# LipSync_Mini_Main_Board.net
KiCad netlist of a schematic drawn in EAGLE
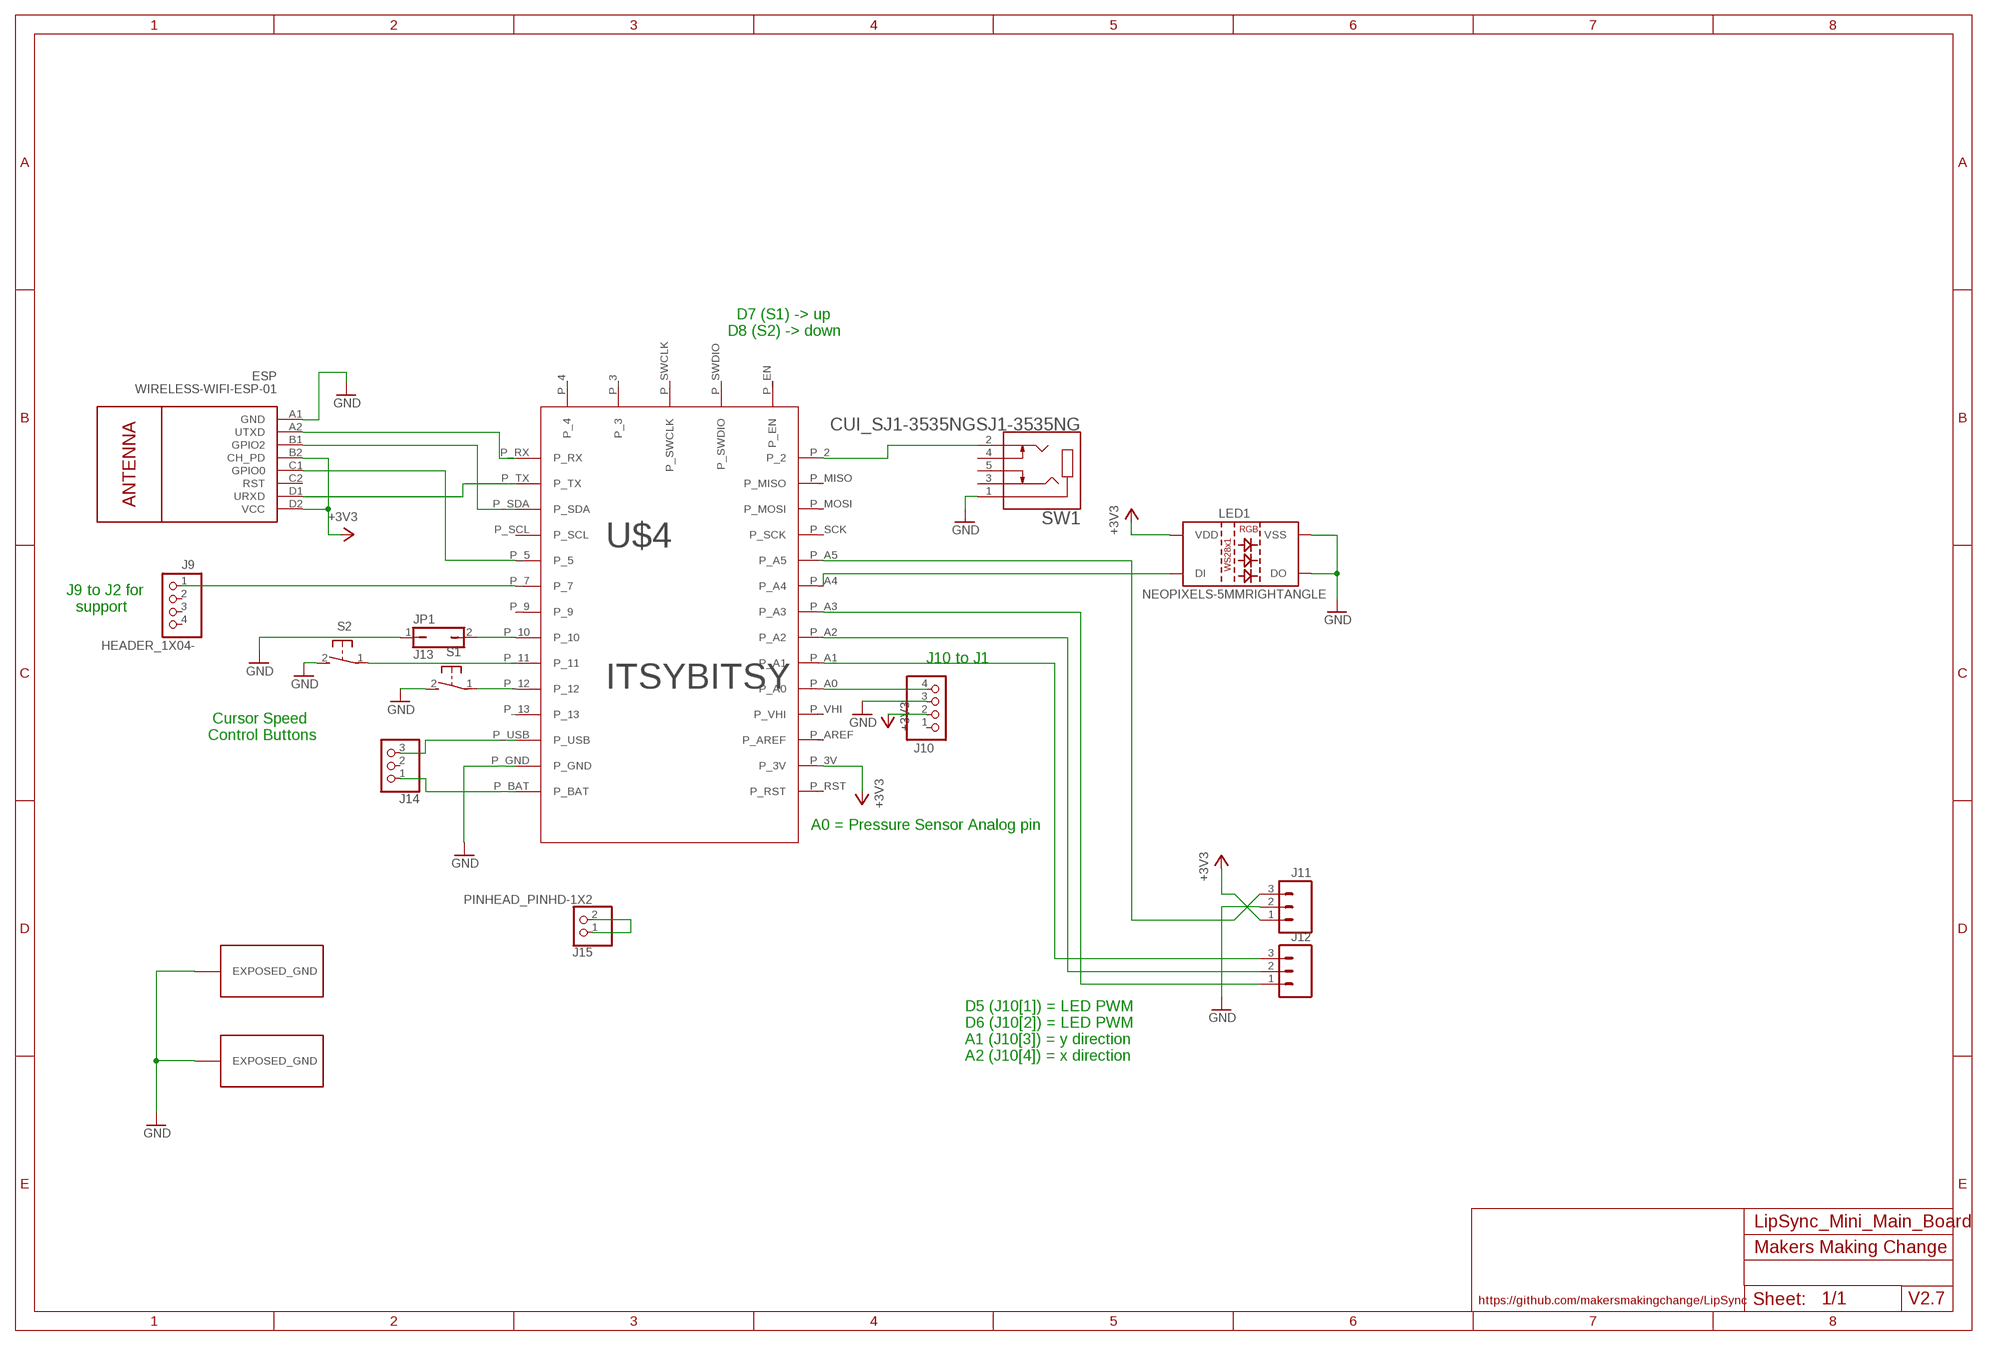
[diagram p0: schematic, sheet 1]

(export (version "E")
  (design (tool "Eeschema 10.0.6"))
  (components
    (comp (ref "ESP")
      (value "WIRELESS-WIFI-ESP-01")
      (footprint "eagle-import:WIRELESS-WIFI-ESP-01")
      (libsource (lib "eagle-import") (part "WIRELESS-WIFI-ESP-01"))
    )
    (comp (ref "J9")
      (value "HEADER_1X04-")
      (footprint "eagle-import:1X04")
      (libsource (lib "eagle-import") (part "HEADER_1X04-"))
    )
    (comp (ref "J10")
      (value "HEADER_1X04-")
      (footprint "eagle-import:1X04")
      (libsource (lib "eagle-import") (part "HEADER_1X04-"))
    )
    (comp (ref "J11")
      (value "HEADER_1X03-/90")
      (footprint "eagle-import:1X03_LOCK_90")
      (libsource (lib "eagle-import") (part "HEADER_1X03-/90"))
    )
    (comp (ref "J12")
      (value "HEADER_1X03-/90")
      (footprint "eagle-import:1X03_LOCK_90")
      (libsource (lib "eagle-import") (part "HEADER_1X03-/90"))
    )
    (comp (ref "J13")
      (value "JP1")
      (footprint "eagle-import:JP1")
      (libsource (lib "eagle-import") (part "JP1"))
    )
    (comp (ref "J14")
      (value "PINHEAD_PINHD-1X3")
      (footprint "eagle-import:PINHEAD_1X03")
      (libsource (lib "eagle-import") (part "PINHEAD_PINHD-1X3"))
    )
    (comp (ref "J15")
      (value "PINHEAD_PINHD-1X2")
      (footprint "eagle-import:PINHEAD_1X02")
      (libsource (lib "eagle-import") (part "PINHEAD_PINHD-1X2"))
    )
    (comp (ref "LED1")
      (value "NEOPIXELS-5MMRIGHTANGLE")
      (footprint "eagle-import:NEOPIXELS-RIGHTANGLE-5MM")
      (libsource (lib "eagle-import") (part "NEOPIXELS-5MMRIGHTANGLE"))
    )
    (comp (ref "S1")
      (value "B3F_31-XXSKINNY")
      (footprint "eagle-import:B3F-31XX-SKINNIER")
      (libsource (lib "eagle-import") (part "B3F_31-XXSKINNY"))
    )
    (comp (ref "S2")
      (value "B3F_31-XXSKINNY")
      (footprint "eagle-import:B3F-31XX-SKINNIER")
      (libsource (lib "eagle-import") (part "B3F_31-XXSKINNY"))
    )
    (comp (ref "SW1")
      (value "CUI_SJ1-3535NGSJ1-3535NG")
      (footprint "eagle-import:CUI_SJ1-3535NG")
      (libsource (lib "eagle-import") (part "CUI_SJ1-3535NGSJ1-3535NG"))
    )
    (comp (ref "U$2")
      (value "EXPOSED_GND")
      (footprint "eagle-import:EXPOSED_GND")
      (libsource (lib "eagle-import") (part "EXPOSED_GND"))
    )
    (comp (ref "U$3")
      (value "EXPOSED_GND")
      (footprint "eagle-import:EXPOSED_GND")
      (libsource (lib "eagle-import") (part "MMC Eagle_13126479_EXPOSED_GND"))
    )
    (comp (ref "U$4")
      (value "ITSYBITSY")
      (footprint "eagle-import:ITSYBITSY")
      (libsource (lib "eagle-import") (part "ITSYBITSY"))
    )
  )
  (nets
    (net (code "1") (name "+3V3") (class "Default")
      (node (ref "ESP") (pin "B2") (pinfunction "CH_PD_B2") (pintype "bidirectional"))
      (node (ref "ESP") (pin "D2") (pinfunction "VCC_D2") (pintype "power_in"))
      (node (ref "J10") (pin "2") (pinfunction "2_2") (pintype "passive"))
      (node (ref "J11") (pin "1") (pinfunction "1_1") (pintype "passive"))
      (node (ref "LED1") (pin "P2") (pinfunction "VDD_P2") (pintype "bidirectional"))
      (node (ref "U$4") (pin "P_3V") (pinfunction "P_3V_P_3V") (pintype "bidirectional"))
    )
    (net (code "2") (name "EXPOSED_GND") (class "Default")
      (node (ref "ESP") (pin "A1") (pinfunction "GND_A1") (pintype "power_in"))
      (node (ref "J10") (pin "3") (pinfunction "3_3") (pintype "passive"))
      (node (ref "J11") (pin "2") (pinfunction "2_2") (pintype "passive"))
      (node (ref "J13") (pin "1") (pinfunction "1_1") (pintype "passive"))
      (node (ref "LED1") (pin "P3") (pinfunction "VSS_P3") (pintype "bidirectional"))
      (node (ref "LED1") (pin "P4") (pinfunction "DO_P4") (pintype "bidirectional"))
      (node (ref "S1") (pin "2") (pinfunction "S_2") (pintype "passive"))
      (node (ref "S2") (pin "2") (pinfunction "S_2") (pintype "passive"))
      (node (ref "SW1") (pin "1") (pinfunction "1_1") (pintype "passive"))
      (node (ref "U$2") (pin "GND1") (pinfunction "EXPOSED_GND_GND1") (pintype "power_in"))
      (node (ref "U$3") (pin "GND1") (pinfunction "EXPOSED_GND_GND1") (pintype "power_in"))
      (node (ref "U$4") (pin "P_GND") (pinfunction "P_GND_P_GND") (pintype "bidirectional"))
    )
    (net (code "3") (name "Net-(ESP-GPIO0)") (class "Default")
      (node (ref "ESP") (pin "C1") (pinfunction "GPIO0_C1") (pintype "bidirectional"))
      (node (ref "U$4") (pin "P_5") (pinfunction "P_5_P_5") (pintype "bidirectional"))
    )
    (net (code "4") (name "Net-(ESP-GPIO2)") (class "Default")
      (node (ref "ESP") (pin "B1") (pinfunction "GPIO2_B1") (pintype "bidirectional"))
      (node (ref "U$4") (pin "P_SDA") (pinfunction "P_SDA_P_SDA") (pintype "bidirectional"))
    )
    (net (code "5") (name "Net-(ESP-URXD)") (class "Default")
      (node (ref "ESP") (pin "D1") (pinfunction "URXD_D1") (pintype "bidirectional"))
      (node (ref "U$4") (pin "P_TX") (pinfunction "P_TX_P_TX") (pintype "bidirectional"))
    )
    (net (code "6") (name "Net-(ESP-UTXD)") (class "Default")
      (node (ref "ESP") (pin "A2") (pinfunction "UTXD_A2") (pintype "bidirectional"))
      (node (ref "U$4") (pin "P_RX") (pinfunction "P_RX_P_RX") (pintype "bidirectional"))
    )
    (net (code "7") (name "Net-(J9-Pad1)") (class "Default")
      (node (ref "J9") (pin "1") (pinfunction "1_1") (pintype "passive"))
      (node (ref "U$4") (pin "P_7") (pinfunction "P_7_P_7") (pintype "bidirectional"))
    )
    (net (code "8") (name "Net-(J10-Pad4)") (class "Default")
      (node (ref "J10") (pin "4") (pinfunction "4_4") (pintype "passive"))
      (node (ref "U$4") (pin "P_A0") (pinfunction "P_A0_P_A0") (pintype "bidirectional"))
    )
    (net (code "9") (name "Net-(J11-Pad3)") (class "Default")
      (node (ref "J11") (pin "3") (pinfunction "3_3") (pintype "passive"))
      (node (ref "U$4") (pin "P_A5") (pinfunction "P_A5_P_A5") (pintype "bidirectional"))
    )
    (net (code "10") (name "Net-(J12-Pad1)") (class "Default")
      (node (ref "J12") (pin "1") (pinfunction "1_1") (pintype "passive"))
      (node (ref "U$4") (pin "P_A3") (pinfunction "P_A3_P_A3") (pintype "bidirectional"))
    )
    (net (code "11") (name "Net-(J12-Pad2)") (class "Default")
      (node (ref "J12") (pin "2") (pinfunction "2_2") (pintype "passive"))
      (node (ref "U$4") (pin "P_A2") (pinfunction "P_A2_P_A2") (pintype "bidirectional"))
    )
    (net (code "12") (name "Net-(J12-Pad3)") (class "Default")
      (node (ref "J12") (pin "3") (pinfunction "3_3") (pintype "passive"))
      (node (ref "U$4") (pin "P_A1") (pinfunction "P_A1_P_A1") (pintype "bidirectional"))
    )
    (net (code "13") (name "Net-(J13-Pad2)") (class "Default")
      (node (ref "J13") (pin "2") (pinfunction "2_2") (pintype "passive"))
      (node (ref "U$4") (pin "P_10") (pinfunction "P_10_P_10") (pintype "bidirectional"))
    )
    (net (code "14") (name "Net-(J14-Pad1)") (class "Default")
      (node (ref "J14") (pin "1") (pinfunction "1_1") (pintype "passive"))
      (node (ref "U$4") (pin "P_BAT") (pinfunction "P_BAT_P_BAT") (pintype "bidirectional"))
    )
    (net (code "15") (name "Net-(J14-Pad3)") (class "Default")
      (node (ref "J14") (pin "3") (pinfunction "3_3") (pintype "passive"))
      (node (ref "U$4") (pin "P_USB") (pinfunction "P_USB_P_USB") (pintype "bidirectional"))
    )
    (net (code "16") (name "Net-(J15-Pad1)") (class "Default")
      (node (ref "J15") (pin "1") (pinfunction "1_1") (pintype "passive"))
      (node (ref "J15") (pin "2") (pinfunction "2_2") (pintype "passive"))
    )
    (net (code "17") (name "Net-(LED1-DI)") (class "Default")
      (node (ref "LED1") (pin "P1") (pinfunction "DI_P1") (pintype "bidirectional"))
      (node (ref "U$4") (pin "P_A4") (pinfunction "P_A4_P_A4") (pintype "bidirectional"))
    )
    (net (code "18") (name "Net-(S1-P)") (class "Default")
      (node (ref "S1") (pin "1") (pinfunction "P_1") (pintype "passive"))
      (node (ref "U$4") (pin "P_12") (pinfunction "P_12_P_12") (pintype "bidirectional"))
    )
    (net (code "19") (name "Net-(S2-P)") (class "Default")
      (node (ref "S2") (pin "1") (pinfunction "P_1") (pintype "passive"))
      (node (ref "U$4") (pin "P_11") (pinfunction "P_11_P_11") (pintype "bidirectional"))
    )
    (net (code "20") (name "Net-(SW1-Pad2)") (class "Default")
      (node (ref "SW1") (pin "2") (pinfunction "2_2") (pintype "passive"))
      (node (ref "U$4") (pin "P_2") (pinfunction "P_2_P_2") (pintype "bidirectional"))
    )
    (net (code "21") (name "unconnected-(ESP-RST-PadC2)") (class "Default")
      (node (ref "ESP") (pin "C2") (pinfunction "RST_C2") (pintype "bidirectional"))
    )
    (net (code "22") (name "unconnected-(J9-Pad2)") (class "Default")
      (node (ref "J9") (pin "2") (pinfunction "2_2") (pintype "passive"))
    )
    (net (code "23") (name "unconnected-(J9-Pad3)") (class "Default")
      (node (ref "J9") (pin "3") (pinfunction "3_3") (pintype "passive"))
    )
    (net (code "24") (name "unconnected-(J9-Pad4)") (class "Default")
      (node (ref "J9") (pin "4") (pinfunction "4_4") (pintype "passive"))
    )
    (net (code "25") (name "unconnected-(J10-Pad1)") (class "Default")
      (node (ref "J10") (pin "1") (pinfunction "1_1") (pintype "passive"))
    )
    (net (code "26") (name "unconnected-(J14-Pad2)") (class "Default")
      (node (ref "J14") (pin "2") (pinfunction "2_2") (pintype "passive"))
    )
    (net (code "27") (name "unconnected-(SW1-Pad3)") (class "Default")
      (node (ref "SW1") (pin "3") (pinfunction "3_3") (pintype "passive"))
    )
    (net (code "28") (name "unconnected-(SW1-Pad4)") (class "Default")
      (node (ref "SW1") (pin "4") (pinfunction "4_4") (pintype "passive"))
    )
    (net (code "29") (name "unconnected-(SW1-Pad5)") (class "Default")
      (node (ref "SW1") (pin "5") (pinfunction "5_5") (pintype "passive"))
    )
    (net (code "30") (name "unconnected-(U$4-PadP_3)") (class "Default")
      (node (ref "U$4") (pin "P_3") (pinfunction "P_3_P_3") (pintype "bidirectional"))
    )
    (net (code "31") (name "unconnected-(U$4-PadP_4)") (class "Default")
      (node (ref "U$4") (pin "P_4") (pinfunction "P_4_P_4") (pintype "bidirectional"))
    )
    (net (code "32") (name "unconnected-(U$4-PadP_9)") (class "Default")
      (node (ref "U$4") (pin "P_9") (pinfunction "P_9_P_9") (pintype "bidirectional"))
    )
    (net (code "33") (name "unconnected-(U$4-PadP_13)") (class "Default")
      (node (ref "U$4") (pin "P_13") (pinfunction "P_13_P_13") (pintype "bidirectional"))
    )
    (net (code "34") (name "unconnected-(U$4-PadP_AREF)") (class "Default")
      (node (ref "U$4") (pin "P_AREF") (pinfunction "P_AREF_P_AREF") (pintype "bidirectional"))
    )
    (net (code "35") (name "unconnected-(U$4-PadP_EN)") (class "Default")
      (node (ref "U$4") (pin "P_EN") (pinfunction "P_EN_P_EN") (pintype "bidirectional"))
    )
    (net (code "36") (name "unconnected-(U$4-PadP_MISO)") (class "Default")
      (node (ref "U$4") (pin "P_MISO") (pinfunction "P_MISO_P_MISO") (pintype "bidirectional"))
    )
    (net (code "37") (name "unconnected-(U$4-PadP_MOSI)") (class "Default")
      (node (ref "U$4") (pin "P_MOSI") (pinfunction "P_MOSI_P_MOSI") (pintype "bidirectional"))
    )
    (net (code "38") (name "unconnected-(U$4-PadP_RST)") (class "Default")
      (node (ref "U$4") (pin "P_RST") (pinfunction "P_RST_P_RST") (pintype "bidirectional"))
    )
    (net (code "39") (name "unconnected-(U$4-PadP_SCK)") (class "Default")
      (node (ref "U$4") (pin "P_SCK") (pinfunction "P_SCK_P_SCK") (pintype "bidirectional"))
    )
    (net (code "40") (name "unconnected-(U$4-PadP_SCL)") (class "Default")
      (node (ref "U$4") (pin "P_SCL") (pinfunction "P_SCL_P_SCL") (pintype "bidirectional"))
    )
    (net (code "41") (name "unconnected-(U$4-PadP_SWCLK)") (class "Default")
      (node (ref "U$4") (pin "P_SWCLK") (pinfunction "P_SWCLK_P_SWCLK") (pintype "bidirectional"))
    )
    (net (code "42") (name "unconnected-(U$4-PadP_SWDIO)") (class "Default")
      (node (ref "U$4") (pin "P_SWDIO") (pinfunction "P_SWDIO_P_SWDIO") (pintype "bidirectional"))
    )
    (net (code "43") (name "unconnected-(U$4-PadP_VHI)") (class "Default")
      (node (ref "U$4") (pin "P_VHI") (pinfunction "P_VHI_P_VHI") (pintype "bidirectional"))
    )
  )
)
